# CompletePCBV4.net
KiCad netlist of a schematic drawn in EAGLE
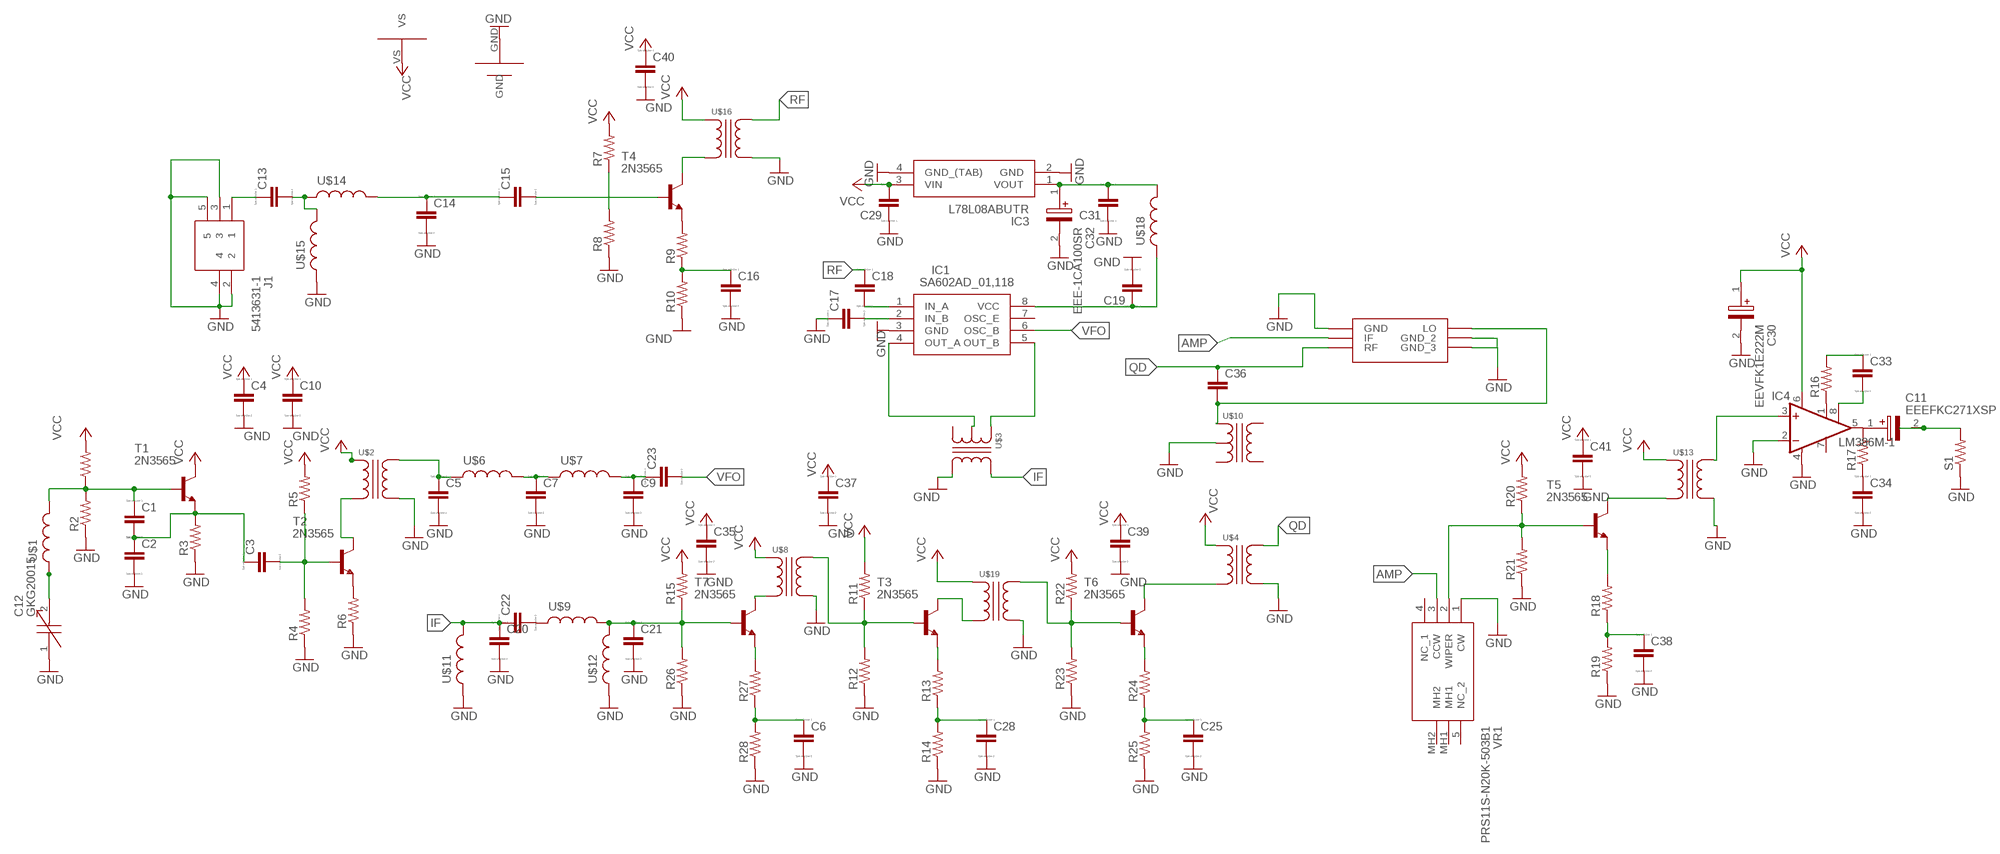
[diagram p0: schematic, sheet 1]

(export (version "E")
  (design (tool "Eeschema 10.0.6"))
  (components
    (comp (ref "C1") (value "C") (footprint "eagle-import:C0805") (libsource (lib "eagle-import") (part "C")))
    (comp (ref "C2") (value "C") (footprint "eagle-import:C0805") (libsource (lib "eagle-import") (part "C")))
    (comp (ref "C3") (value "C") (footprint "eagle-import:C0805") (libsource (lib "eagle-import") (part "C")))
    (comp (ref "C4") (value "C") (footprint "eagle-import:C0805") (libsource (lib "eagle-import") (part "C")))
    (comp (ref "C5") (value "C") (footprint "eagle-import:C0805") (libsource (lib "eagle-import") (part "C")))
    (comp (ref "C6") (value "C") (footprint "eagle-import:C0805") (libsource (lib "eagle-import") (part "C")))
    (comp (ref "C7") (value "C") (footprint "eagle-import:C0805") (libsource (lib "eagle-import") (part "C")))
    (comp (ref "C9") (value "C") (footprint "eagle-import:C0805") (libsource (lib "eagle-import") (part "C")))
    (comp (ref "C10")
      (value "C")
      (footprint "eagle-import:C0805")
      (libsource (lib "eagle-import") (part "C"))
    )
    (comp (ref "C11")
      (value "EEEFKC271XSP")
      (footprint "eagle-import:FKSV(D8)")
      (libsource (lib "eagle-import") (part "EEEFKC271XSP"))
    )
    (comp (ref "C12")
      (value "GKG20015")
      (footprint "eagle-import:GKG20015")
      (fields (field (name "MOUSER_PART_NUMBER") "659-GKG20015"))
      (libsource (lib "eagle-import") (part "GKG20015"))
    )
    (comp (ref "C13")
      (value "C")
      (footprint "eagle-import:C0805")
      (libsource (lib "eagle-import") (part "C"))
    )
    (comp (ref "C14")
      (value "C")
      (footprint "eagle-import:C0805")
      (libsource (lib "eagle-import") (part "C"))
    )
    (comp (ref "C15")
      (value "C")
      (footprint "eagle-import:C0805")
      (libsource (lib "eagle-import") (part "C"))
    )
    (comp (ref "C16")
      (value "C")
      (footprint "eagle-import:C0805")
      (libsource (lib "eagle-import") (part "C"))
    )
    (comp (ref "C17")
      (value "C")
      (footprint "eagle-import:C0805")
      (libsource (lib "eagle-import") (part "C"))
    )
    (comp (ref "C18")
      (value "C")
      (footprint "eagle-import:C0805")
      (libsource (lib "eagle-import") (part "C"))
    )
    (comp (ref "C19")
      (value "C")
      (footprint "eagle-import:C0805")
      (libsource (lib "eagle-import") (part "C"))
    )
    (comp (ref "C20")
      (value "C")
      (footprint "eagle-import:C0805")
      (libsource (lib "eagle-import") (part "C"))
    )
    (comp (ref "C21")
      (value "C")
      (footprint "eagle-import:C0805")
      (libsource (lib "eagle-import") (part "C"))
    )
    (comp (ref "C22")
      (value "C")
      (footprint "eagle-import:C0805")
      (libsource (lib "eagle-import") (part "C"))
    )
    (comp (ref "C23")
      (value "C")
      (footprint "eagle-import:C0805")
      (libsource (lib "eagle-import") (part "C"))
    )
    (comp (ref "C25")
      (value "C")
      (footprint "eagle-import:C0805")
      (libsource (lib "eagle-import") (part "C"))
    )
    (comp (ref "C28")
      (value "C")
      (footprint "eagle-import:C0805")
      (libsource (lib "eagle-import") (part "C"))
    )
    (comp (ref "C29")
      (value "C")
      (footprint "eagle-import:C0805")
      (libsource (lib "eagle-import") (part "C"))
    )
    (comp (ref "C30")
      (value "EEVFK1E222M")
      (footprint "eagle-import:FKV(J16)")
      (libsource (lib "eagle-import") (part "EEVFK1E222M"))
    )
    (comp (ref "C31")
      (value "C")
      (footprint "eagle-import:C0805")
      (libsource (lib "eagle-import") (part "C"))
    )
    (comp (ref "C32")
      (value "EEE-1CA100SR")
      (footprint "eagle-import:SV(B)")
      (fields (field (name "MOUSER_PART_NUMBER") "667-EEE-1CA100SR"))
      (libsource (lib "eagle-import") (part "EEE-1CA100SR"))
    )
    (comp (ref "C33")
      (value "C")
      (footprint "eagle-import:C0805")
      (libsource (lib "eagle-import") (part "C"))
    )
    (comp (ref "C34")
      (value "CC1206")
      (footprint "eagle-import:C1206")
      (libsource (lib "eagle-import") (part "CC1206"))
    )
    (comp (ref "C35")
      (value "C")
      (footprint "eagle-import:C0805")
      (libsource (lib "eagle-import") (part "C"))
    )
    (comp (ref "C36")
      (value "C-EUC0805")
      (footprint "eagle-import:C0805")
      (libsource (lib "eagle-import") (part "C-EUC0805"))
    )
    (comp (ref "C37")
      (value "C")
      (footprint "eagle-import:C0805")
      (libsource (lib "eagle-import") (part "C"))
    )
    (comp (ref "C38")
      (value "C")
      (footprint "eagle-import:C0805")
      (libsource (lib "eagle-import") (part "C"))
    )
    (comp (ref "C39")
      (value "C")
      (footprint "eagle-import:C0805")
      (libsource (lib "eagle-import") (part "C"))
    )
    (comp (ref "C40")
      (value "C")
      (footprint "eagle-import:C0805")
      (libsource (lib "eagle-import") (part "C"))
    )
    (comp (ref "C41")
      (value "C")
      (footprint "eagle-import:C0805")
      (libsource (lib "eagle-import") (part "C"))
    )
    (comp (ref "IC1")
      (value "SA602AD_01,118")
      (footprint "eagle-import:SOIC127P600X175-8N")
      (fields
        (field (name "MANUFACTURER_PART_NUMBER") "SA602AD/01,118")
        (field (name "MOUSER_PART_NUMBER") "771-SA602AD/01-T")
      )
      (libsource (lib "eagle-import") (part "SA602AD_01,118"))
    )
    (comp (ref "IC3")
      (value "L78L08ABUTR")
      (footprint "eagle-import:ST-SOT-89")
      (fields (field (name "MOUSER_PART_NUMBER") "511-L78L08ABU"))
      (libsource (lib "eagle-import") (part "L78L08ABUTR"))
    )
    (comp (ref "IC4")
      (value "LM386M-1")
      (footprint "eagle-import:SO08")
      (libsource (lib "eagle-import") (part "LM386?-M1"))
    )
    (comp (ref "J1")
      (value "5413631-1")
      (footprint "eagle-import:54136311")
      (fields (field (name "MOUSER_PART_NUMBER") "571-5413631-1"))
      (libsource (lib "eagle-import") (part "5413631-1"))
    )
    (comp (ref "R1")
      (value "R-US_R0805")
      (footprint "eagle-import:R0805")
      (libsource (lib "eagle-import") (part "resistor_348_R-US_R0805"))
    )
    (comp (ref "R2")
      (value "R-US_R0805")
      (footprint "eagle-import:R0805")
      (libsource (lib "eagle-import") (part "resistor_348_R-US_R0805"))
    )
    (comp (ref "R3")
      (value "R-US_R0805")
      (footprint "eagle-import:R0805")
      (libsource (lib "eagle-import") (part "resistor_348_R-US_R0805"))
    )
    (comp (ref "R4")
      (value "R-US_R0805")
      (footprint "eagle-import:R0805")
      (libsource (lib "eagle-import") (part "resistor_348_R-US_R0805"))
    )
    (comp (ref "R5")
      (value "R-US_R0805")
      (footprint "eagle-import:R0805")
      (libsource (lib "eagle-import") (part "resistor_348_R-US_R0805"))
    )
    (comp (ref "R6")
      (value "R-US_R0805")
      (footprint "eagle-import:R0805")
      (libsource (lib "eagle-import") (part "resistor_348_R-US_R0805"))
    )
    (comp (ref "R7")
      (value "R-US_R0805")
      (footprint "eagle-import:R0805")
      (libsource (lib "eagle-import") (part "resistor_348_R-US_R0805"))
    )
    (comp (ref "R8")
      (value "R-US_R0805")
      (footprint "eagle-import:R0805")
      (libsource (lib "eagle-import") (part "resistor_348_R-US_R0805"))
    )
    (comp (ref "R9")
      (value "R-US_R0805")
      (footprint "eagle-import:R0805")
      (libsource (lib "eagle-import") (part "resistor_348_R-US_R0805"))
    )
    (comp (ref "R10")
      (value "R-US_R0805")
      (footprint "eagle-import:R0805")
      (libsource (lib "eagle-import") (part "resistor_348_R-US_R0805"))
    )
    (comp (ref "R11")
      (value "R-US_R0805")
      (footprint "eagle-import:R0805")
      (libsource (lib "eagle-import") (part "resistor_348_R-US_R0805"))
    )
    (comp (ref "R12")
      (value "R-US_R0805")
      (footprint "eagle-import:R0805")
      (libsource (lib "eagle-import") (part "resistor_348_R-US_R0805"))
    )
    (comp (ref "R13")
      (value "R-US_R0805")
      (footprint "eagle-import:R0805")
      (libsource (lib "eagle-import") (part "resistor_348_R-US_R0805"))
    )
    (comp (ref "R14")
      (value "R-US_R0805")
      (footprint "eagle-import:R0805")
      (libsource (lib "eagle-import") (part "resistor_348_R-US_R0805"))
    )
    (comp (ref "R15")
      (value "R-US_R0805")
      (footprint "eagle-import:R0805")
      (libsource (lib "eagle-import") (part "resistor_348_R-US_R0805"))
    )
    (comp (ref "R16")
      (value "R-US_R0805")
      (footprint "eagle-import:R0805")
      (libsource (lib "eagle-import") (part "resistor_348_R-US_R0805"))
    )
    (comp (ref "R17")
      (value "R-US_R0805")
      (footprint "eagle-import:R0805")
      (libsource (lib "eagle-import") (part "resistor_348_R-US_R0805"))
    )
    (comp (ref "R18")
      (value "R-US_R0805")
      (footprint "eagle-import:R0805")
      (libsource (lib "eagle-import") (part "resistor_348_R-US_R0805"))
    )
    (comp (ref "R19")
      (value "R-US_R0805")
      (footprint "eagle-import:R0805")
      (libsource (lib "eagle-import") (part "resistor_348_R-US_R0805"))
    )
    (comp (ref "R20")
      (value "R-US_R0805")
      (footprint "eagle-import:R0805")
      (libsource (lib "eagle-import") (part "resistor_348_R-US_R0805"))
    )
    (comp (ref "R21")
      (value "R-US_R0805")
      (footprint "eagle-import:R0805")
      (libsource (lib "eagle-import") (part "resistor_348_R-US_R0805"))
    )
    (comp (ref "R22")
      (value "R-US_R0805")
      (footprint "eagle-import:R0805")
      (libsource (lib "eagle-import") (part "resistor_348_R-US_R0805"))
    )
    (comp (ref "R23")
      (value "R-US_R0805")
      (footprint "eagle-import:R0805")
      (libsource (lib "eagle-import") (part "resistor_348_R-US_R0805"))
    )
    (comp (ref "R24")
      (value "R-US_R0805")
      (footprint "eagle-import:R0805")
      (libsource (lib "eagle-import") (part "resistor_348_R-US_R0805"))
    )
    (comp (ref "R25")
      (value "R-US_R0805")
      (footprint "eagle-import:R0805")
      (libsource (lib "eagle-import") (part "resistor_348_R-US_R0805"))
    )
    (comp (ref "R26")
      (value "R-US_R0805")
      (footprint "eagle-import:R0805")
      (libsource (lib "eagle-import") (part "resistor_348_R-US_R0805"))
    )
    (comp (ref "R27")
      (value "R-US_R0805")
      (footprint "eagle-import:R0805")
      (libsource (lib "eagle-import") (part "resistor_348_R-US_R0805"))
    )
    (comp (ref "R28")
      (value "R-US_R0805")
      (footprint "eagle-import:R0805")
      (libsource (lib "eagle-import") (part "resistor_348_R-US_R0805"))
    )
    (comp (ref "S1")
      (value "R-US_0207/5V")
      (footprint "eagle-import:0207_5V")
      (libsource (lib "eagle-import") (part "R-US_0207/5V"))
    )
    (comp (ref "T1")
      (value "2N3565")
      (footprint "eagle-import:TO92")
      (libsource (lib "eagle-import") (part "2N3565"))
    )
    (comp (ref "T2")
      (value "2N3565")
      (footprint "eagle-import:TO92")
      (libsource (lib "eagle-import") (part "2N3565"))
    )
    (comp (ref "T3")
      (value "2N3565")
      (footprint "eagle-import:TO92")
      (libsource (lib "eagle-import") (part "2N3565"))
    )
    (comp (ref "T4")
      (value "2N3565")
      (footprint "eagle-import:TO92")
      (libsource (lib "eagle-import") (part "2N3565"))
    )
    (comp (ref "T5")
      (value "2N3565")
      (footprint "eagle-import:TO92")
      (libsource (lib "eagle-import") (part "2N3565"))
    )
    (comp (ref "T6")
      (value "2N3565")
      (footprint "eagle-import:TO92")
      (libsource (lib "eagle-import") (part "2N3565"))
    )
    (comp (ref "T7")
      (value "2N3565")
      (footprint "eagle-import:TO92")
      (libsource (lib "eagle-import") (part "2N3565"))
    )
    (comp (ref "U$1")
      (value "WOUNDINDUCTOR")
      (footprint "eagle-import:WOUNDINDUCTOR")
      (libsource (lib "eagle-import") (part "WOUNDINDUCTOR"))
    )
    (comp (ref "U$2")
      (value "RFTRANSFORMER")
      (footprint "eagle-import:RFTRABSFORMER")
      (libsource (lib "eagle-import") (part "RFTRANSFORMER"))
    )
    (comp (ref "U$3")
      (value "42IF123")
      (footprint "eagle-import:42IF123")
      (libsource (lib "eagle-import") (part "42IF123"))
    )
    (comp (ref "U$4")
      (value "RFTRANSFORMER")
      (footprint "eagle-import:RFTRABSFORMER")
      (libsource (lib "eagle-import") (part "RFTRANSFORMER"))
    )
    (comp (ref "U$5")
      (value "ALLIGATORCLIPS")
      (footprint "eagle-import:ALLIGATORCONNECTOR")
      (libsource (lib "eagle-import") (part "ALLIGATORCLIPS"))
    )
    (comp (ref "U$6")
      (value "WOUNDINDUCTOR")
      (footprint "eagle-import:WOUNDINDUCTOR")
      (libsource (lib "eagle-import") (part "WOUNDINDUCTOR"))
    )
    (comp (ref "U$7")
      (value "WOUNDINDUCTOR")
      (footprint "eagle-import:WOUNDINDUCTOR")
      (libsource (lib "eagle-import") (part "WOUNDINDUCTOR"))
    )
    (comp (ref "U$8")
      (value "RFTRANSFORMER")
      (footprint "eagle-import:RFTRABSFORMER")
      (libsource (lib "eagle-import") (part "RFTRANSFORMER"))
    )
    (comp (ref "U$9")
      (value "WOUNDINDUCTOR")
      (footprint "eagle-import:WOUNDINDUCTOR")
      (libsource (lib "eagle-import") (part "WOUNDINDUCTOR"))
    )
    (comp (ref "U$10")
      (value "42IF123")
      (footprint "eagle-import:42IF123")
      (libsource (lib "eagle-import") (part "42IF123"))
    )
    (comp (ref "U$11")
      (value "WOUNDINDUCTOR")
      (footprint "eagle-import:WOUNDINDUCTOR")
      (libsource (lib "eagle-import") (part "WOUNDINDUCTOR"))
    )
    (comp (ref "U$12")
      (value "WOUNDINDUCTOR")
      (footprint "eagle-import:WOUNDINDUCTOR")
      (libsource (lib "eagle-import") (part "WOUNDINDUCTOR"))
    )
    (comp (ref "U$13")
      (value "RFTRANSFORMER")
      (footprint "eagle-import:RFTRABSFORMER")
      (libsource (lib "eagle-import") (part "RFTRANSFORMER"))
    )
    (comp (ref "U$14")
      (value "WOUNDINDUCTOR")
      (footprint "eagle-import:WOUNDINDUCTOR")
      (libsource (lib "eagle-import") (part "WOUNDINDUCTOR"))
    )
    (comp (ref "U$15")
      (value "WOUNDINDUCTOR")
      (footprint "eagle-import:WOUNDINDUCTOR")
      (libsource (lib "eagle-import") (part "WOUNDINDUCTOR"))
    )
    (comp (ref "U$16")
      (value "RFTRANSFORMER")
      (footprint "eagle-import:RFTRABSFORMER")
      (libsource (lib "eagle-import") (part "RFTRANSFORMER"))
    )
    (comp (ref "U$17")
      (value "ADE-1")
      (footprint "eagle-import:ADE-1")
      (libsource (lib "eagle-import") (part "ADE-1"))
    )
    (comp (ref "U$18")
      (value "WOUNDINDUCTOR")
      (footprint "eagle-import:WOUNDINDUCTOR")
      (libsource (lib "eagle-import") (part "WOUNDINDUCTOR"))
    )
    (comp (ref "U$19")
      (value "RFTRANSFORMER")
      (footprint "eagle-import:RFTRABSFORMER")
      (libsource (lib "eagle-import") (part "RFTRANSFORMER"))
    )
    (comp (ref "VR1")
      (value "PRS11S-N20K-503B1")
      (footprint "eagle-import:PRS11SN20K503B1")
      (fields (field (name "MOUSER_PART_NUMBER") "652-PRS11SN20K503B1"))
      (libsource (lib "eagle-import") (part "PRS11S-N20K-503B1"))
    )
  )
  (nets
    (net (code "1") (name "AMP") (class "Default")
      (node (ref "U$17") (pin "IF") (pinfunction "IF_IF") (pintype "bidirectional"))
      (node (ref "VR1") (pin "3") (pinfunction "CCW_3") (pintype "bidirectional"))
    )
    (net (code "2") (name "GND") (class "Default")
      (node (ref "C10") (pin "2") (pinfunction "2_2") (pintype "passive"))
      (node (ref "C12") (pin "1") (pinfunction "1_1") (pintype "bidirectional"))
      (node (ref "C14") (pin "2") (pinfunction "2_2") (pintype "passive"))
      (node (ref "C16") (pin "2") (pinfunction "2_2") (pintype "passive"))
      (node (ref "C17") (pin "1") (pinfunction "1_1") (pintype "passive"))
      (node (ref "C19") (pin "2") (pinfunction "2_2") (pintype "passive"))
      (node (ref "C2") (pin "2") (pinfunction "2_2") (pintype "passive"))
      (node (ref "C20") (pin "2") (pinfunction "2_2") (pintype "passive"))
      (node (ref "C21") (pin "2") (pinfunction "2_2") (pintype "passive"))
      (node (ref "C25") (pin "2") (pinfunction "2_2") (pintype "passive"))
      (node (ref "C28") (pin "2") (pinfunction "2_2") (pintype "passive"))
      (node (ref "C29") (pin "1") (pinfunction "1_1") (pintype "passive"))
      (node (ref "C30") (pin "2") (pinfunction "-_2") (pintype "bidirectional"))
      (node (ref "C31") (pin "1") (pinfunction "1_1") (pintype "passive"))
      (node (ref "C32") (pin "2") (pinfunction "-_2") (pintype "bidirectional"))
      (node (ref "C34") (pin "2") (pinfunction "2_2") (pintype "passive"))
      (node (ref "C35") (pin "2") (pinfunction "2_2") (pintype "passive"))
      (node (ref "C37") (pin "2") (pinfunction "2_2") (pintype "passive"))
      (node (ref "C38") (pin "2") (pinfunction "2_2") (pintype "passive"))
      (node (ref "C39") (pin "2") (pinfunction "2_2") (pintype "passive"))
      (node (ref "C4") (pin "2") (pinfunction "2_2") (pintype "passive"))
      (node (ref "C40") (pin "2") (pinfunction "2_2") (pintype "passive"))
      (node (ref "C41") (pin "2") (pinfunction "2_2") (pintype "passive"))
      (node (ref "C5") (pin "2") (pinfunction "2_2") (pintype "passive"))
      (node (ref "C6") (pin "2") (pinfunction "2_2") (pintype "passive"))
      (node (ref "C7") (pin "2") (pinfunction "2_2") (pintype "passive"))
      (node (ref "C9") (pin "2") (pinfunction "2_2") (pintype "passive"))
      (node (ref "IC1") (pin "3") (pinfunction "GND_3") (pintype "power_in"))
      (node (ref "IC3") (pin "2") (pinfunction "GND_2") (pintype "power_in"))
      (node (ref "IC3") (pin "4") (pinfunction "GND_(TAB)_4") (pintype "power_in"))
      (node (ref "IC4") (pin "2") (pinfunction "-IN_2") (pintype "input"))
      (node (ref "IC4") (pin "4") (pinfunction "GND_4") (pintype "power_in"))
      (node (ref "J1") (pin "2") (pinfunction "2_2") (pintype "bidirectional"))
      (node (ref "J1") (pin "3") (pinfunction "3_3") (pintype "bidirectional"))
      (node (ref "J1") (pin "4") (pinfunction "4_4") (pintype "bidirectional"))
      (node (ref "J1") (pin "5") (pinfunction "5_5") (pintype "bidirectional"))
      (node (ref "R10") (pin "1") (pinfunction "1_1") (pintype "passive"))
      (node (ref "R12") (pin "1") (pinfunction "1_1") (pintype "passive"))
      (node (ref "R14") (pin "1") (pinfunction "1_1") (pintype "passive"))
      (node (ref "R19") (pin "1") (pinfunction "1_1") (pintype "passive"))
      (node (ref "R2") (pin "1") (pinfunction "1_1") (pintype "passive"))
      (node (ref "R21") (pin "1") (pinfunction "1_1") (pintype "passive"))
      (node (ref "R23") (pin "1") (pinfunction "1_1") (pintype "passive"))
      (node (ref "R25") (pin "1") (pinfunction "1_1") (pintype "passive"))
      (node (ref "R26") (pin "1") (pinfunction "1_1") (pintype "passive"))
      (node (ref "R28") (pin "1") (pinfunction "1_1") (pintype "passive"))
      (node (ref "R3") (pin "1") (pinfunction "1_1") (pintype "passive"))
      (node (ref "R4") (pin "1") (pinfunction "1_1") (pintype "passive"))
      (node (ref "R6") (pin "1") (pinfunction "1_1") (pintype "passive"))
      (node (ref "R8") (pin "1") (pinfunction "1_1") (pintype "passive"))
      (node (ref "S1") (pin "1") (pinfunction "1_1") (pintype "passive"))
      (node (ref "U$10") (pin "P$1") (pinfunction "P$5_P$1") (pintype "bidirectional"))
      (node (ref "U$11") (pin "1") (pinfunction "1_1") (pintype "bidirectional"))
      (node (ref "U$12") (pin "1") (pinfunction "1_1") (pintype "bidirectional"))
      (node (ref "U$13") (pin "P$4") (pinfunction "P$3_P$4") (pintype "bidirectional"))
      (node (ref "U$15") (pin "1") (pinfunction "1_1") (pintype "bidirectional"))
      (node (ref "U$16") (pin "P$4") (pinfunction "P$3_P$4") (pintype "bidirectional"))
      (node (ref "U$17") (pin "GND") (pinfunction "GND_GND") (pintype "bidirectional"))
      (node (ref "U$17") (pin "GND2") (pinfunction "GND_2_GND2") (pintype "bidirectional"))
      (node (ref "U$17") (pin "GND3") (pinfunction "GND_3_GND3") (pintype "bidirectional"))
      (node (ref "U$19") (pin "P$4") (pinfunction "P$3_P$4") (pintype "bidirectional"))
      (node (ref "U$2") (pin "P$4") (pinfunction "P$3_P$4") (pintype "bidirectional"))
      (node (ref "U$3") (pin "P$4") (pinfunction "P$3_P$4") (pintype "bidirectional"))
      (node (ref "U$4") (pin "P$4") (pinfunction "P$3_P$4") (pintype "bidirectional"))
      (node (ref "U$5") (pin "GND") (pinfunction "GND_GND") (pintype "bidirectional"))
      (node (ref "U$8") (pin "P$4") (pinfunction "P$3_P$4") (pintype "bidirectional"))
      (node (ref "VR1") (pin "1") (pinfunction "CW_1") (pintype "bidirectional"))
    )
    (net (code "3") (name "IF") (class "Default")
      (node (ref "C20") (pin "1") (pinfunction "1_1") (pintype "passive"))
      (node (ref "C22") (pin "1") (pinfunction "1_1") (pintype "passive"))
      (node (ref "U$11") (pin "2") (pinfunction "2_2") (pintype "bidirectional"))
      (node (ref "U$3") (pin "P$5") (pinfunction "P$4_P$5") (pintype "bidirectional"))
    )
    (net (code "4") (name "Net-(C6-Pad1)") (class "Default")
      (node (ref "C6") (pin "1") (pinfunction "1_1") (pintype "passive"))
      (node (ref "R27") (pin "1") (pinfunction "1_1") (pintype "passive"))
      (node (ref "R28") (pin "2") (pinfunction "2_2") (pintype "passive"))
    )
    (net (code "5") (name "Net-(C7-Pad1)") (class "Default")
      (node (ref "C7") (pin "1") (pinfunction "1_1") (pintype "passive"))
      (node (ref "U$6") (pin "2") (pinfunction "2_2") (pintype "bidirectional"))
      (node (ref "U$7") (pin "1") (pinfunction "1_1") (pintype "bidirectional"))
    )
    (net (code "6") (name "Net-(C11-+)") (class "Default")
      (node (ref "C11") (pin "1") (pinfunction "+_1") (pintype "bidirectional"))
      (node (ref "IC4") (pin "5") (pinfunction "OUT_5") (pintype "output"))
      (node (ref "R17") (pin "2") (pinfunction "2_2") (pintype "passive"))
    )
    (net (code "7") (name "Net-(C11--)") (class "Default")
      (node (ref "C11") (pin "2") (pinfunction "-_2") (pintype "bidirectional"))
      (node (ref "S1") (pin "2") (pinfunction "2_2") (pintype "passive"))
    )
    (net (code "8") (name "Net-(C12-Pad2)") (class "Default")
      (node (ref "C12") (pin "2") (pinfunction "2_2") (pintype "bidirectional"))
      (node (ref "U$1") (pin "1") (pinfunction "1_1") (pintype "bidirectional"))
    )
    (net (code "9") (name "Net-(C13-Pad1)") (class "Default")
      (node (ref "C13") (pin "1") (pinfunction "1_1") (pintype "passive"))
      (node (ref "J1") (pin "1") (pinfunction "1_1") (pintype "bidirectional"))
    )
    (net (code "10") (name "Net-(C13-Pad2)") (class "Default")
      (node (ref "C13") (pin "2") (pinfunction "2_2") (pintype "passive"))
      (node (ref "U$14") (pin "1") (pinfunction "1_1") (pintype "bidirectional"))
      (node (ref "U$15") (pin "2") (pinfunction "2_2") (pintype "bidirectional"))
    )
    (net (code "11") (name "Net-(C14-Pad1)") (class "Default")
      (node (ref "C14") (pin "1") (pinfunction "1_1") (pintype "passive"))
      (node (ref "C15") (pin "1") (pinfunction "1_1") (pintype "passive"))
      (node (ref "U$14") (pin "2") (pinfunction "2_2") (pintype "bidirectional"))
    )
    (net (code "12") (name "Net-(C16-Pad1)") (class "Default")
      (node (ref "C16") (pin "1") (pinfunction "1_1") (pintype "passive"))
      (node (ref "R10") (pin "2") (pinfunction "2_2") (pintype "passive"))
      (node (ref "R9") (pin "1") (pinfunction "1_1") (pintype "passive"))
    )
    (net (code "13") (name "Net-(C22-Pad2)") (class "Default")
      (node (ref "C22") (pin "2") (pinfunction "2_2") (pintype "passive"))
      (node (ref "U$9") (pin "1") (pinfunction "1_1") (pintype "bidirectional"))
    )
    (net (code "14") (name "Net-(C23-Pad1)") (class "Default")
      (node (ref "C23") (pin "1") (pinfunction "1_1") (pintype "passive"))
      (node (ref "C9") (pin "1") (pinfunction "1_1") (pintype "passive"))
      (node (ref "U$7") (pin "2") (pinfunction "2_2") (pintype "bidirectional"))
    )
    (net (code "15") (name "Net-(C25-Pad1)") (class "Default")
      (node (ref "C25") (pin "1") (pinfunction "1_1") (pintype "passive"))
      (node (ref "R24") (pin "1") (pinfunction "1_1") (pintype "passive"))
      (node (ref "R25") (pin "2") (pinfunction "2_2") (pintype "passive"))
    )
    (net (code "16") (name "Net-(C28-Pad1)") (class "Default")
      (node (ref "C28") (pin "1") (pinfunction "1_1") (pintype "passive"))
      (node (ref "R13") (pin "1") (pinfunction "1_1") (pintype "passive"))
      (node (ref "R14") (pin "2") (pinfunction "2_2") (pintype "passive"))
    )
    (net (code "17") (name "Net-(C32-+)") (class "Default")
      (node (ref "C31") (pin "2") (pinfunction "2_2") (pintype "passive"))
      (node (ref "C32") (pin "1") (pinfunction "+_1") (pintype "bidirectional"))
      (node (ref "IC3") (pin "1") (pinfunction "VOUT_1") (pintype "output"))
      (node (ref "U$18") (pin "2") (pinfunction "2_2") (pintype "bidirectional"))
    )
    (net (code "18") (name "Net-(C33-Pad1)") (class "Default")
      (node (ref "C33") (pin "1") (pinfunction "1_1") (pintype "passive"))
      (node (ref "R16") (pin "2") (pinfunction "2_2") (pintype "passive"))
    )
    (net (code "19") (name "Net-(C33-Pad2)") (class "Default")
      (node (ref "C33") (pin "2") (pinfunction "2_2") (pintype "passive"))
      (node (ref "IC4") (pin "8") (pinfunction "GAIN_8") (pintype "passive"))
    )
    (net (code "20") (name "Net-(C34-Pad1)") (class "Default")
      (node (ref "C34") (pin "1") (pinfunction "1_1") (pintype "passive"))
      (node (ref "R17") (pin "1") (pinfunction "1_1") (pintype "passive"))
    )
    (net (code "21") (name "Net-(C38-Pad1)") (class "Default")
      (node (ref "C38") (pin "1") (pinfunction "1_1") (pintype "passive"))
      (node (ref "R18") (pin "1") (pinfunction "1_1") (pintype "passive"))
      (node (ref "R19") (pin "2") (pinfunction "2_2") (pintype "passive"))
    )
    (net (code "22") (name "Net-(IC1-IN_A)") (class "Default")
      (node (ref "C18") (pin "2") (pinfunction "2_2") (pintype "passive"))
      (node (ref "IC1") (pin "1") (pinfunction "IN_A_1") (pintype "input"))
    )
    (net (code "23") (name "Net-(IC1-IN_B)") (class "Default")
      (node (ref "C17") (pin "2") (pinfunction "2_2") (pintype "passive"))
      (node (ref "IC1") (pin "2") (pinfunction "IN_B_2") (pintype "input"))
    )
    (net (code "24") (name "Net-(IC1-OUT_A)") (class "Default")
      (node (ref "IC1") (pin "4") (pinfunction "OUT_A_4") (pintype "output"))
      (node (ref "U$3") (pin "P$1") (pinfunction "P$5_P$1") (pintype "bidirectional"))
    )
    (net (code "25") (name "Net-(IC1-OUT_B)") (class "Default")
      (node (ref "IC1") (pin "5") (pinfunction "OUT_B_5") (pintype "output"))
      (node (ref "U$3") (pin "P$2") (pinfunction "P$1_P$2") (pintype "bidirectional"))
    )
    (net (code "26") (name "Net-(IC1-VCC)") (class "Default")
      (node (ref "C19") (pin "1") (pinfunction "1_1") (pintype "passive"))
      (node (ref "IC1") (pin "8") (pinfunction "VCC_8") (pintype "power_in"))
      (node (ref "U$18") (pin "1") (pinfunction "1_1") (pintype "bidirectional"))
    )
    (net (code "27") (name "Net-(IC4-+IN)") (class "Default")
      (node (ref "IC4") (pin "3") (pinfunction "+IN_3") (pintype "input"))
      (node (ref "U$13") (pin "P$3") (pinfunction "P$4_P$3") (pintype "bidirectional"))
    )
    (net (code "28") (name "Net-(IC4-GAIN-Pad1)") (class "Default")
      (node (ref "IC4") (pin "1") (pinfunction "GAIN_1") (pintype "passive"))
      (node (ref "R16") (pin "1") (pinfunction "1_1") (pintype "passive"))
    )
    (net (code "29") (name "Net-(R7-Pad1)") (class "Default")
      (node (ref "R7") (pin "1") (pinfunction "1_1") (pintype "passive"))
      (node (ref "R8") (pin "2") (pinfunction "2_2") (pintype "passive"))
    )
    (net (code "30") (name "Net-(T1-B)") (class "Default")
      (node (ref "C1") (pin "1") (pinfunction "1_1") (pintype "passive"))
      (node (ref "R1") (pin "1") (pinfunction "1_1") (pintype "passive"))
      (node (ref "R2") (pin "2") (pinfunction "2_2") (pintype "passive"))
      (node (ref "T1") (pin "2") (pinfunction "B_2") (pintype "passive"))
      (node (ref "U$1") (pin "2") (pinfunction "2_2") (pintype "bidirectional"))
    )
    (net (code "31") (name "Net-(T1-E)") (class "Default")
      (node (ref "C1") (pin "2") (pinfunction "2_2") (pintype "passive"))
      (node (ref "C2") (pin "1") (pinfunction "1_1") (pintype "passive"))
      (node (ref "C3") (pin "1") (pinfunction "1_1") (pintype "passive"))
      (node (ref "R3") (pin "2") (pinfunction "2_2") (pintype "passive"))
      (node (ref "T1") (pin "3") (pinfunction "E_3") (pintype "passive"))
    )
    (net (code "32") (name "Net-(T2-B)") (class "Default")
      (node (ref "C3") (pin "2") (pinfunction "2_2") (pintype "passive"))
      (node (ref "R4") (pin "2") (pinfunction "2_2") (pintype "passive"))
      (node (ref "R5") (pin "1") (pinfunction "1_1") (pintype "passive"))
      (node (ref "T2") (pin "2") (pinfunction "B_2") (pintype "passive"))
    )
    (net (code "33") (name "Net-(T2-C)") (class "Default")
      (node (ref "T2") (pin "1") (pinfunction "C_1") (pintype "passive"))
      (node (ref "U$2") (pin "P$2") (pinfunction "P$2_P$2") (pintype "bidirectional"))
    )
    (net (code "34") (name "Net-(T2-E)") (class "Default")
      (node (ref "R6") (pin "2") (pinfunction "2_2") (pintype "passive"))
      (node (ref "T2") (pin "3") (pinfunction "E_3") (pintype "passive"))
    )
    (net (code "35") (name "Net-(T3-B)") (class "Default")
      (node (ref "R11") (pin "1") (pinfunction "1_1") (pintype "passive"))
      (node (ref "R12") (pin "2") (pinfunction "2_2") (pintype "passive"))
      (node (ref "T3") (pin "2") (pinfunction "B_2") (pintype "passive"))
      (node (ref "U$8") (pin "P$3") (pinfunction "P$4_P$3") (pintype "bidirectional"))
    )
    (net (code "36") (name "Net-(T3-C)") (class "Default")
      (node (ref "T3") (pin "1") (pinfunction "C_1") (pintype "passive"))
      (node (ref "U$19") (pin "P$2") (pinfunction "P$2_P$2") (pintype "bidirectional"))
    )
    (net (code "37") (name "Net-(T3-E)") (class "Default")
      (node (ref "R13") (pin "2") (pinfunction "2_2") (pintype "passive"))
      (node (ref "T3") (pin "3") (pinfunction "E_3") (pintype "passive"))
    )
    (net (code "38") (name "Net-(T4-B)") (class "Default")
      (node (ref "C15") (pin "2") (pinfunction "2_2") (pintype "passive"))
      (node (ref "T4") (pin "2") (pinfunction "B_2") (pintype "passive"))
    )
    (net (code "39") (name "Net-(T4-C)") (class "Default")
      (node (ref "T4") (pin "1") (pinfunction "C_1") (pintype "passive"))
      (node (ref "U$16") (pin "P$2") (pinfunction "P$2_P$2") (pintype "bidirectional"))
    )
    (net (code "40") (name "Net-(T4-E)") (class "Default")
      (node (ref "R9") (pin "2") (pinfunction "2_2") (pintype "passive"))
      (node (ref "T4") (pin "3") (pinfunction "E_3") (pintype "passive"))
    )
    (net (code "41") (name "Net-(T5-B)") (class "Default")
      (node (ref "R20") (pin "1") (pinfunction "1_1") (pintype "passive"))
      (node (ref "R21") (pin "2") (pinfunction "2_2") (pintype "passive"))
      (node (ref "T5") (pin "2") (pinfunction "B_2") (pintype "passive"))
      (node (ref "VR1") (pin "2") (pinfunction "WIPER_2") (pintype "bidirectional"))
    )
    (net (code "42") (name "Net-(T5-C)") (class "Default")
      (node (ref "T5") (pin "1") (pinfunction "C_1") (pintype "passive"))
      (node (ref "U$13") (pin "P$2") (pinfunction "P$2_P$2") (pintype "bidirectional"))
    )
    (net (code "43") (name "Net-(T5-E)") (class "Default")
      (node (ref "R18") (pin "2") (pinfunction "2_2") (pintype "passive"))
      (node (ref "T5") (pin "3") (pinfunction "E_3") (pintype "passive"))
    )
    (net (code "44") (name "Net-(T6-B)") (class "Default")
      (node (ref "R22") (pin "1") (pinfunction "1_1") (pintype "passive"))
      (node (ref "R23") (pin "2") (pinfunction "2_2") (pintype "passive"))
      (node (ref "T6") (pin "2") (pinfunction "B_2") (pintype "passive"))
      (node (ref "U$19") (pin "P$3") (pinfunction "P$4_P$3") (pintype "bidirectional"))
    )
    (net (code "45") (name "Net-(T6-C)") (class "Default")
      (node (ref "T6") (pin "1") (pinfunction "C_1") (pintype "passive"))
      (node (ref "U$4") (pin "P$2") (pinfunction "P$2_P$2") (pintype "bidirectional"))
    )
    (net (code "46") (name "Net-(T6-E)") (class "Default")
      (node (ref "R24") (pin "2") (pinfunction "2_2") (pintype "passive"))
      (node (ref "T6") (pin "3") (pinfunction "E_3") (pintype "passive"))
    )
    (net (code "47") (name "Net-(T7-B)") (class "Default")
      (node (ref "C21") (pin "1") (pinfunction "1_1") (pintype "passive"))
      (node (ref "R15") (pin "1") (pinfunction "1_1") (pintype "passive"))
      (node (ref "R26") (pin "2") (pinfunction "2_2") (pintype "passive"))
      (node (ref "T7") (pin "2") (pinfunction "B_2") (pintype "passive"))
      (node (ref "U$12") (pin "2") (pinfunction "2_2") (pintype "bidirectional"))
      (node (ref "U$9") (pin "2") (pinfunction "2_2") (pintype "bidirectional"))
    )
    (net (code "48") (name "Net-(T7-C)") (class "Default")
      (node (ref "T7") (pin "1") (pinfunction "C_1") (pintype "passive"))
      (node (ref "U$8") (pin "P$2") (pinfunction "P$2_P$2") (pintype "bidirectional"))
    )
    (net (code "49") (name "Net-(T7-E)") (class "Default")
      (node (ref "R27") (pin "2") (pinfunction "2_2") (pintype "passive"))
      (node (ref "T7") (pin "3") (pinfunction "E_3") (pintype "passive"))
    )
    (net (code "50") (name "Net-(U$2-P$4)") (class "Default")
      (node (ref "C5") (pin "1") (pinfunction "1_1") (pintype "passive"))
      (node (ref "U$2") (pin "P$3") (pinfunction "P$4_P$3") (pintype "bidirectional"))
      (node (ref "U$6") (pin "1") (pinfunction "1_1") (pintype "bidirectional"))
    )
    (net (code "51") (name "Net-(U$10-P$1)") (class "Default")
      (node (ref "C36") (pin "2") (pinfunction "2_2") (pintype "passive"))
      (node (ref "U$10") (pin "P$2") (pinfunction "P$1_P$2") (pintype "bidirectional"))
      (node (ref "U$17") (pin "LO") (pinfunction "LO_LO") (pintype "bidirectional"))
    )
    (net (code "52") (name "QD") (class "Default")
      (node (ref "C36") (pin "1") (pinfunction "1_1") (pintype "passive"))
      (node (ref "U$17") (pin "RF") (pinfunction "RF_RF") (pintype "bidirectional"))
      (node (ref "U$4") (pin "P$3") (pinfunction "P$4_P$3") (pintype "bidirectional"))
    )
    (net (code "53") (name "RF") (class "Default")
      (node (ref "C18") (pin "1") (pinfunction "1_1") (pintype "passive"))
      (node (ref "U$16") (pin "P$3") (pinfunction "P$4_P$3") (pintype "bidirectional"))
    )
    (net (code "54") (name "VCC") (class "Default")
      (node (ref "C10") (pin "1") (pinfunction "1_1") (pintype "passive"))
      (node (ref "C29") (pin "2") (pinfunction "2_2") (pintype "passive"))
      (node (ref "C30") (pin "1") (pinfunction "+_1") (pintype "bidirectional"))
      (node (ref "C35") (pin "1") (pinfunction "1_1") (pintype "passive"))
      (node (ref "C37") (pin "1") (pinfunction "1_1") (pintype "passive"))
      (node (ref "C39") (pin "1") (pinfunction "1_1") (pintype "passive"))
      (node (ref "C4") (pin "1") (pinfunction "1_1") (pintype "passive"))
      (node (ref "C40") (pin "1") (pinfunction "1_1") (pintype "passive"))
      (node (ref "C41") (pin "1") (pinfunction "1_1") (pintype "passive"))
      (node (ref "IC3") (pin "3") (pinfunction "VIN_3") (pintype "input"))
      (node (ref "IC4") (pin "6") (pinfunction "VS_6") (pintype "power_in"))
      (node (ref "R1") (pin "2") (pinfunction "2_2") (pintype "passive"))
      (node (ref "R11") (pin "2") (pinfunction "2_2") (pintype "passive"))
      (node (ref "R15") (pin "2") (pinfunction "2_2") (pintype "passive"))
      (node (ref "R20") (pin "2") (pinfunction "2_2") (pintype "passive"))
      (node (ref "R22") (pin "2") (pinfunction "2_2") (pintype "passive"))
      (node (ref "R5") (pin "2") (pinfunction "2_2") (pintype "passive"))
      (node (ref "R7") (pin "2") (pinfunction "2_2") (pintype "passive"))
      (node (ref "T1") (pin "1") (pinfunction "C_1") (pintype "passive"))
      (node (ref "U$13") (pin "P$1") (pinfunction "P$1_P$1") (pintype "bidirectional"))
      (node (ref "U$16") (pin "P$1") (pinfunction "P$1_P$1") (pintype "bidirectional"))
      (node (ref "U$19") (pin "P$1") (pinfunction "P$1_P$1") (pintype "bidirectional"))
      (node (ref "U$2") (pin "P$1") (pinfunction "P$1_P$1") (pintype "bidirectional"))
      (node (ref "U$4") (pin "P$1") (pinfunction "P$1_P$1") (pintype "bidirectional"))
      (node (ref "U$5") (pin "VS") (pinfunction "VS_VS") (pintype "bidirectional"))
      (node (ref "U$8") (pin "P$1") (pinfunction "P$1_P$1") (pintype "bidirectional"))
    )
    (net (code "55") (name "VFO") (class "Default")
      (node (ref "C23") (pin "2") (pinfunction "2_2") (pintype "passive"))
      (node (ref "IC1") (pin "6") (pinfunction "OSC_B_6") (pintype "bidirectional"))
    )
    (net (code "56") (name "unconnected-(IC1-OSC_E-Pad7)") (class "Default")
      (node (ref "IC1") (pin "7") (pinfunction "OSC_E_7") (pintype "bidirectional"))
    )
    (net (code "57") (name "unconnected-(IC4-BYPASS-Pad7)") (class "Default")
      (node (ref "IC4") (pin "7") (pinfunction "BYPASS_7") (pintype "passive"))
    )
    (net (code "58") (name "unconnected-(U$3-P$2-PadP$3)") (class "Default")
      (node (ref "U$3") (pin "P$3") (pinfunction "P$2_P$3") (pintype "bidirectional"))
    )
    (net (code "59") (name "unconnected-(U$10-P$2-PadP$3)") (class "Default")
      (node (ref "U$10") (pin "P$3") (pinfunction "P$2_P$3") (pintype "bidirectional"))
    )
    (net (code "60") (name "unconnected-(U$10-P$3-PadP$4)") (class "Default")
      (node (ref "U$10") (pin "P$4") (pinfunction "P$3_P$4") (pintype "bidirectional"))
    )
    (net (code "61") (name "unconnected-(U$10-P$4-PadP$5)") (class "Default")
      (node (ref "U$10") (pin "P$5") (pinfunction "P$4_P$5") (pintype "bidirectional"))
    )
    (net (code "62") (name "unconnected-(VR1-NC_1-Pad4)") (class "Default")
      (node (ref "VR1") (pin "4") (pinfunction "NC_1_4") (pintype "bidirectional"))
    )
    (net (code "63") (name "unconnected-(VR1-NC_2-Pad5)") (class "Default")
      (node (ref "VR1") (pin "5") (pinfunction "NC_2_5") (pintype "bidirectional"))
    )
    (net (code "64") (name "unconnected-(VR1-PadMH1)") (class "Default")
      (node (ref "VR1") (pin "MH1") (pinfunction "MH1_MH1") (pintype "bidirectional"))
    )
    (net (code "65") (name "unconnected-(VR1-PadMH2)") (class "Default")
      (node (ref "VR1") (pin "MH2") (pinfunction "MH2_MH2") (pintype "bidirectional"))
    )
  )
)
